# main.net
KiCad netlist of a schematic drawn in EAGLE
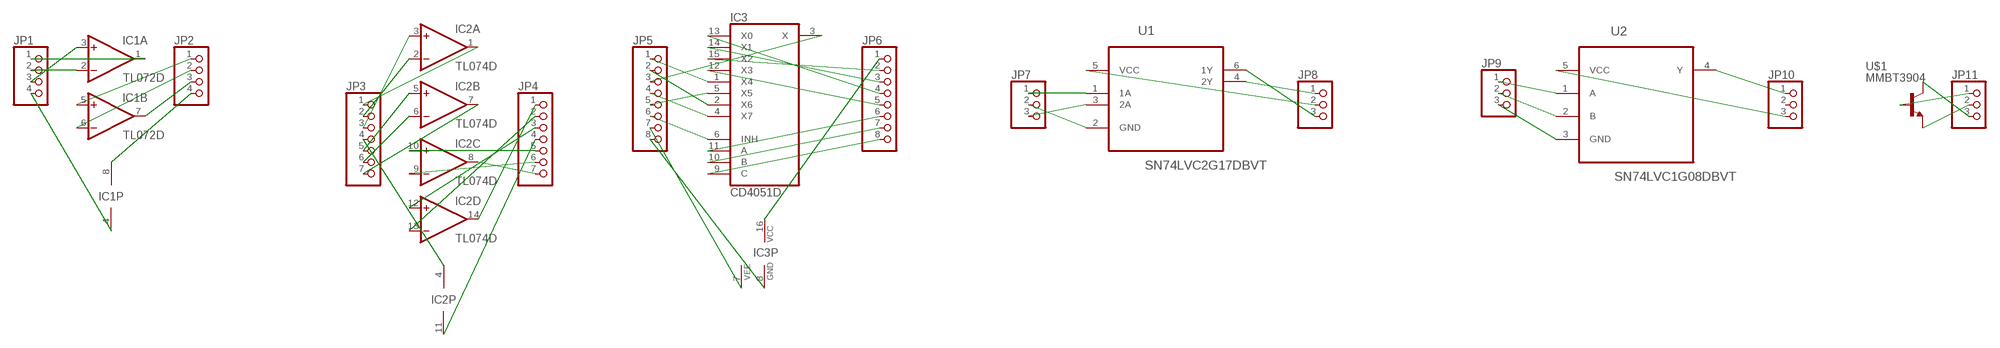
[diagram p0: schematic, sheet 1]

(export (version "E")
  (design (tool "Eeschema 10.0.6"))
  (components
    (comp (ref "IC1")
      (value "TL072D")
      (footprint "eagle-import:SO08")
      (libsource (lib "eagle-import") (part "TL072D"))
    )
    (comp (ref "IC2")
      (value "TL074D")
      (footprint "eagle-import:SO14")
      (libsource (lib "eagle-import") (part "TL074D"))
    )
    (comp (ref "IC3")
      (value "CD4051D")
      (footprint "eagle-import:SO16")
      (libsource (lib "eagle-import") (part "CD4051D"))
    )
    (comp (ref "JP1")
      (value "PINHD-1X4/OCT")
      (footprint "eagle-import:1X04_OCT")
      (libsource (lib "eagle-import") (part "PINHD-1X4/OCT"))
    )
    (comp (ref "JP2")
      (value "PINHD-1X4/OCT")
      (footprint "eagle-import:1X04_OCT")
      (libsource (lib "eagle-import") (part "PINHD-1X4/OCT"))
    )
    (comp (ref "JP3")
      (value "PINHD-1X7/OCT")
      (footprint "eagle-import:1X07_OCT")
      (libsource (lib "eagle-import") (part "PINHD-1X7/OCT"))
    )
    (comp (ref "JP4")
      (value "PINHD-1X7/OCT")
      (footprint "eagle-import:1X07_OCT")
      (libsource (lib "eagle-import") (part "PINHD-1X7/OCT"))
    )
    (comp (ref "JP5")
      (value "PINHD-1X8")
      (footprint "eagle-import:1X08")
      (libsource (lib "eagle-import") (part "PINHD-1X8"))
    )
    (comp (ref "JP6")
      (value "PINHD-1X8")
      (footprint "eagle-import:1X08")
      (libsource (lib "eagle-import") (part "PINHD-1X8"))
    )
    (comp (ref "JP7")
      (value "PINHD-1X3/OCT")
      (footprint "eagle-import:1X03_OCT")
      (libsource (lib "eagle-import") (part "PINHD-1X3/OCT"))
    )
    (comp (ref "JP8")
      (value "PINHD-1X3/OCT")
      (footprint "eagle-import:1X03_OCT")
      (libsource (lib "eagle-import") (part "PINHD-1X3/OCT"))
    )
    (comp (ref "JP9")
      (value "PINHD-1X3/OCT")
      (footprint "eagle-import:1X03_OCT")
      (libsource (lib "eagle-import") (part "PINHD-1X3/OCT"))
    )
    (comp (ref "JP10")
      (value "PINHD-1X3/OCT")
      (footprint "eagle-import:1X03_OCT")
      (libsource (lib "eagle-import") (part "PINHD-1X3/OCT"))
    )
    (comp (ref "JP11")
      (value "PINHD-1X3/OCT")
      (footprint "eagle-import:1X03_OCT")
      (libsource (lib "eagle-import") (part "PINHD-1X3/OCT"))
    )
    (comp (ref "U$1")
      (value "MMBT3904")
      (footprint "eagle-import:SOT23")
      (libsource (lib "eagle-import") (part "MMBT3904"))
    )
    (comp (ref "U1")
      (value "SN74LVC2G17DBVT")
      (footprint "eagle-import:SOT95P280X145-6N")
      (libsource (lib "eagle-import") (part "SN74LVC2G17DBVT"))
    )
    (comp (ref "U2")
      (value "SN74LVC1G08DBVT")
      (footprint "eagle-import:SOT95P280X145-5N")
      (libsource (lib "eagle-import") (part "SN74LVC1G08DBVT"))
    )
  )
  (nets
    (net (code "1") (name "Net-(IC1A-+IN)") (class "Default")
      (node (ref "IC1") (pin "3") (pinfunction "+IN_3") (pintype "input"))
      (node (ref "JP1") (pin "3") (pinfunction "3_3") (pintype "passive"))
    )
    (net (code "2") (name "Net-(IC1A--IN)") (class "Default")
      (node (ref "IC1") (pin "2") (pinfunction "-IN_2") (pintype "input"))
      (node (ref "JP1") (pin "2") (pinfunction "2_2") (pintype "passive"))
    )
    (net (code "3") (name "Net-(IC1A-OUT)") (class "Default")
      (node (ref "IC1") (pin "1") (pinfunction "OUT_1") (pintype "output"))
      (node (ref "JP1") (pin "1") (pinfunction "1_1") (pintype "passive"))
    )
    (net (code "4") (name "Net-(IC1B-+IN)") (class "Default")
      (node (ref "IC1") (pin "5") (pinfunction "+IN_5") (pintype "input"))
      (node (ref "JP2") (pin "1") (pinfunction "1_1") (pintype "passive"))
    )
    (net (code "5") (name "Net-(IC1B--IN)") (class "Default")
      (node (ref "IC1") (pin "6") (pinfunction "-IN_6") (pintype "input"))
      (node (ref "JP2") (pin "2") (pinfunction "2_2") (pintype "passive"))
    )
    (net (code "6") (name "Net-(IC1B-OUT)") (class "Default")
      (node (ref "IC1") (pin "7") (pinfunction "OUT_7") (pintype "output"))
      (node (ref "JP2") (pin "3") (pinfunction "3_3") (pintype "passive"))
    )
    (net (code "7") (name "Net-(IC1C-V+)") (class "Default")
      (node (ref "IC1") (pin "8") (pinfunction "V+_8") (pintype "power_in"))
      (node (ref "JP2") (pin "4") (pinfunction "4_4") (pintype "passive"))
    )
    (net (code "8") (name "Net-(IC1C-V-)") (class "Default")
      (node (ref "IC1") (pin "4") (pinfunction "V-_4") (pintype "power_in"))
      (node (ref "JP1") (pin "4") (pinfunction "4_4") (pintype "passive"))
    )
    (net (code "9") (name "Net-(IC2A-+IN)") (class "Default")
      (node (ref "IC2") (pin "3") (pinfunction "+IN_3") (pintype "input"))
      (node (ref "JP3") (pin "3") (pinfunction "3_3") (pintype "passive"))
    )
    (net (code "10") (name "Net-(IC2A--IN)") (class "Default")
      (node (ref "IC2") (pin "2") (pinfunction "-IN_2") (pintype "input"))
      (node (ref "JP3") (pin "2") (pinfunction "2_2") (pintype "passive"))
    )
    (net (code "11") (name "Net-(IC2A-OUT)") (class "Default")
      (node (ref "IC2") (pin "1") (pinfunction "OUT_1") (pintype "output"))
      (node (ref "JP3") (pin "1") (pinfunction "1_1") (pintype "passive"))
    )
    (net (code "12") (name "Net-(IC2B-+IN)") (class "Default")
      (node (ref "IC2") (pin "5") (pinfunction "+IN_5") (pintype "input"))
      (node (ref "JP3") (pin "5") (pinfunction "5_5") (pintype "passive"))
    )
    (net (code "13") (name "Net-(IC2B--IN)") (class "Default")
      (node (ref "IC2") (pin "6") (pinfunction "-IN_6") (pintype "input"))
      (node (ref "JP3") (pin "6") (pinfunction "6_6") (pintype "passive"))
    )
    (net (code "14") (name "Net-(IC2B-OUT)") (class "Default")
      (node (ref "IC2") (pin "7") (pinfunction "OUT_7") (pintype "output"))
      (node (ref "JP3") (pin "7") (pinfunction "7_7") (pintype "passive"))
    )
    (net (code "15") (name "Net-(IC2C-+IN)") (class "Default")
      (node (ref "IC2") (pin "10") (pinfunction "+IN_10") (pintype "input"))
      (node (ref "JP4") (pin "5") (pinfunction "5_5") (pintype "passive"))
    )
    (net (code "16") (name "Net-(IC2C--IN)") (class "Default")
      (node (ref "IC2") (pin "9") (pinfunction "-IN_9") (pintype "input"))
      (node (ref "JP4") (pin "6") (pinfunction "6_6") (pintype "passive"))
    )
    (net (code "17") (name "Net-(IC2C-OUT)") (class "Default")
      (node (ref "IC2") (pin "8") (pinfunction "OUT_8") (pintype "output"))
      (node (ref "JP4") (pin "7") (pinfunction "7_7") (pintype "passive"))
    )
    (net (code "18") (name "Net-(IC2D-+IN)") (class "Default")
      (node (ref "IC2") (pin "12") (pinfunction "+IN_12") (pintype "input"))
      (node (ref "JP4") (pin "3") (pinfunction "3_3") (pintype "passive"))
    )
    (net (code "19") (name "Net-(IC2D--IN)") (class "Default")
      (node (ref "IC2") (pin "13") (pinfunction "-IN_13") (pintype "input"))
      (node (ref "JP4") (pin "2") (pinfunction "2_2") (pintype "passive"))
    )
    (net (code "20") (name "Net-(IC2D-OUT)") (class "Default")
      (node (ref "IC2") (pin "14") (pinfunction "OUT_14") (pintype "output"))
      (node (ref "JP4") (pin "1") (pinfunction "1_1") (pintype "passive"))
    )
    (net (code "21") (name "Net-(IC2E-V+)") (class "Default")
      (node (ref "IC2") (pin "4") (pinfunction "V+_4") (pintype "power_in"))
      (node (ref "JP3") (pin "4") (pinfunction "4_4") (pintype "passive"))
    )
    (net (code "22") (name "Net-(IC2E-V-)") (class "Default")
      (node (ref "IC2") (pin "11") (pinfunction "V-_11") (pintype "power_in"))
      (node (ref "JP4") (pin "4") (pinfunction "4_4") (pintype "passive"))
    )
    (net (code "23") (name "Net-(IC3A-A)") (class "Default")
      (node (ref "IC3") (pin "11") (pinfunction "A_11") (pintype "input"))
      (node (ref "JP6") (pin "6") (pinfunction "6_6") (pintype "passive"))
    )
    (net (code "24") (name "Net-(IC3A-B)") (class "Default")
      (node (ref "IC3") (pin "10") (pinfunction "B_10") (pintype "input"))
      (node (ref "JP6") (pin "7") (pinfunction "7_7") (pintype "passive"))
    )
    (net (code "25") (name "Net-(IC3A-C)") (class "Default")
      (node (ref "IC3") (pin "9") (pinfunction "C_9") (pintype "input"))
      (node (ref "JP6") (pin "8") (pinfunction "8_8") (pintype "passive"))
    )
    (net (code "26") (name "Net-(IC3A-INH)") (class "Default")
      (node (ref "IC3") (pin "6") (pinfunction "INH_6") (pintype "input"))
      (node (ref "JP5") (pin "6") (pinfunction "6_6") (pintype "passive"))
    )
    (net (code "27") (name "Net-(IC3A-X)") (class "Default")
      (node (ref "IC3") (pin "3") (pinfunction "X_3") (pintype "bidirectional"))
      (node (ref "JP5") (pin "3") (pinfunction "3_3") (pintype "passive"))
    )
    (net (code "28") (name "Net-(IC3A-X0)") (class "Default")
      (node (ref "IC3") (pin "13") (pinfunction "X0_13") (pintype "bidirectional"))
      (node (ref "JP6") (pin "4") (pinfunction "4_4") (pintype "passive"))
    )
    (net (code "29") (name "Net-(IC3A-X1)") (class "Default")
      (node (ref "IC3") (pin "14") (pinfunction "X1_14") (pintype "bidirectional"))
      (node (ref "JP6") (pin "3") (pinfunction "3_3") (pintype "passive"))
    )
    (net (code "30") (name "Net-(IC3A-X2)") (class "Default")
      (node (ref "IC3") (pin "15") (pinfunction "X2_15") (pintype "bidirectional"))
      (node (ref "JP6") (pin "2") (pinfunction "2_2") (pintype "passive"))
    )
    (net (code "31") (name "Net-(IC3A-X3)") (class "Default")
      (node (ref "IC3") (pin "12") (pinfunction "X3_12") (pintype "bidirectional"))
      (node (ref "JP6") (pin "5") (pinfunction "5_5") (pintype "passive"))
    )
    (net (code "32") (name "Net-(IC3A-X4)") (class "Default")
      (node (ref "IC3") (pin "1") (pinfunction "X4_1") (pintype "bidirectional"))
      (node (ref "JP5") (pin "1") (pinfunction "1_1") (pintype "passive"))
    )
    (net (code "33") (name "Net-(IC3A-X5)") (class "Default")
      (node (ref "IC3") (pin "5") (pinfunction "X5_5") (pintype "bidirectional"))
      (node (ref "JP5") (pin "5") (pinfunction "5_5") (pintype "passive"))
    )
    (net (code "34") (name "Net-(IC3A-X6)") (class "Default")
      (node (ref "IC3") (pin "2") (pinfunction "X6_2") (pintype "bidirectional"))
      (node (ref "JP5") (pin "2") (pinfunction "2_2") (pintype "passive"))
    )
    (net (code "35") (name "Net-(IC3A-X7)") (class "Default")
      (node (ref "IC3") (pin "4") (pinfunction "X7_4") (pintype "bidirectional"))
      (node (ref "JP5") (pin "4") (pinfunction "4_4") (pintype "passive"))
    )
    (net (code "36") (name "Net-(IC3B-GND)") (class "Default")
      (node (ref "IC3") (pin "8") (pinfunction "GND_8") (pintype "power_in"))
      (node (ref "JP5") (pin "8") (pinfunction "8_8") (pintype "passive"))
    )
    (net (code "37") (name "Net-(IC3B-VCC)") (class "Default")
      (node (ref "IC3") (pin "16") (pinfunction "VCC_16") (pintype "power_in"))
      (node (ref "JP6") (pin "1") (pinfunction "1_1") (pintype "passive"))
    )
    (net (code "38") (name "Net-(IC3B-VEE)") (class "Default")
      (node (ref "IC3") (pin "7") (pinfunction "VEE_7") (pintype "power_in"))
      (node (ref "JP5") (pin "7") (pinfunction "7_7") (pintype "passive"))
    )
    (net (code "39") (name "Net-(U$1-B)") (class "Default")
      (node (ref "JP11") (pin "1") (pinfunction "1_1") (pintype "passive"))
      (node (ref "U$1") (pin "1") (pinfunction "B_1") (pintype "passive"))
    )
    (net (code "40") (name "Net-(U$1-C)") (class "Default")
      (node (ref "JP11") (pin "3") (pinfunction "3_3") (pintype "passive"))
      (node (ref "U$1") (pin "3") (pinfunction "C_3") (pintype "passive"))
    )
    (net (code "41") (name "Net-(U$1-E)") (class "Default")
      (node (ref "JP11") (pin "2") (pinfunction "2_2") (pintype "passive"))
      (node (ref "U$1") (pin "2") (pinfunction "E_2") (pintype "passive"))
    )
    (net (code "42") (name "Net-(U1-1A)") (class "Default")
      (node (ref "JP7") (pin "1") (pinfunction "1_1") (pintype "passive"))
      (node (ref "U1") (pin "1") (pinfunction "1A_1") (pintype "input"))
    )
    (net (code "43") (name "Net-(U1-1Y)") (class "Default")
      (node (ref "JP8") (pin "3") (pinfunction "3_3") (pintype "passive"))
      (node (ref "U1") (pin "6") (pinfunction "1Y_6") (pintype "output"))
    )
    (net (code "44") (name "Net-(U1-2A)") (class "Default")
      (node (ref "JP7") (pin "3") (pinfunction "3_3") (pintype "passive"))
      (node (ref "U1") (pin "3") (pinfunction "2A_3") (pintype "input"))
    )
    (net (code "45") (name "Net-(U1-2Y)") (class "Default")
      (node (ref "JP8") (pin "1") (pinfunction "1_1") (pintype "passive"))
      (node (ref "U1") (pin "4") (pinfunction "2Y_4") (pintype "output"))
    )
    (net (code "46") (name "Net-(U1-GND)") (class "Default")
      (node (ref "JP7") (pin "2") (pinfunction "2_2") (pintype "passive"))
      (node (ref "U1") (pin "2") (pinfunction "GND_2") (pintype "passive"))
    )
    (net (code "47") (name "Net-(U1-VCC)") (class "Default")
      (node (ref "JP8") (pin "2") (pinfunction "2_2") (pintype "passive"))
      (node (ref "U1") (pin "5") (pinfunction "VCC_5") (pintype "power_in"))
    )
    (net (code "48") (name "Net-(U2-A)") (class "Default")
      (node (ref "JP9") (pin "1") (pinfunction "1_1") (pintype "passive"))
      (node (ref "U2") (pin "1") (pinfunction "A_1") (pintype "input"))
    )
    (net (code "49") (name "Net-(U2-B)") (class "Default")
      (node (ref "JP9") (pin "2") (pinfunction "2_2") (pintype "passive"))
      (node (ref "U2") (pin "2") (pinfunction "B_2") (pintype "input"))
    )
    (net (code "50") (name "Net-(U2-GND)") (class "Default")
      (node (ref "JP9") (pin "3") (pinfunction "3_3") (pintype "passive"))
      (node (ref "U2") (pin "3") (pinfunction "GND_3") (pintype "passive"))
    )
    (net (code "51") (name "Net-(U2-VCC)") (class "Default")
      (node (ref "JP10") (pin "3") (pinfunction "3_3") (pintype "passive"))
      (node (ref "U2") (pin "5") (pinfunction "VCC_5") (pintype "power_in"))
    )
    (net (code "52") (name "Net-(U2-Y)") (class "Default")
      (node (ref "JP10") (pin "1") (pinfunction "1_1") (pintype "passive"))
      (node (ref "U2") (pin "4") (pinfunction "Y_4") (pintype "output"))
    )
    (net (code "53") (name "unconnected-(JP10-Pad2)") (class "Default")
      (node (ref "JP10") (pin "2") (pinfunction "2_2") (pintype "passive"))
    )
  )
)
